# AirFlow_Sensor.net
KiCad netlist of a schematic drawn in EAGLE
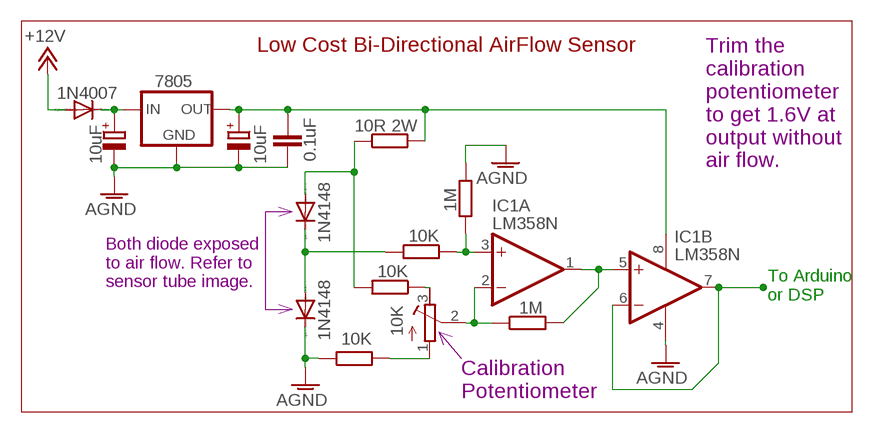
[diagram p0: schematic, sheet 1]

(export (version "E")
  (design (tool "Eeschema 10.0.6"))
  (components
    (comp (ref "C1")
      (value "0.1uF")
      (footprint "eagle-import:C025-025X050")
      (libsource (lib "eagle-import") (part "C-EU025-025X050"))
    )
    (comp (ref "C2")
      (value "10uF")
      (footprint "eagle-import:E2,5-6")
      (libsource (lib "eagle-import") (part "CPOL-EUE2.5-6"))
    )
    (comp (ref "C4")
      (value "10uF")
      (footprint "eagle-import:E2,5-6")
      (libsource (lib "eagle-import") (part "CPOL-EUE2.5-6"))
    )
    (comp (ref "CALIBRATION")
      (value "10K")
      (footprint "eagle-import:RTRIM64W")
      (libsource (lib "eagle-import") (part "R-TRIMM64W"))
    )
    (comp (ref "D2")
      (value "1N4148")
      (footprint "eagle-import:DO35-7")
      (libsource (lib "eagle-import") (part "1N4148DO35-7"))
    )
    (comp (ref "D3")
      (value "1N4148")
      (footprint "eagle-import:DO35-7")
      (libsource (lib "eagle-import") (part "1N4148DO35-7"))
    )
    (comp (ref "D4")
      (value "1N4007")
      (footprint "eagle-import:DO41-10")
      (libsource (lib "eagle-import") (part "1N4004"))
    )
    (comp (ref "IC1")
      (value "LM358N")
      (footprint "eagle-import:DIL08")
      (libsource (lib "eagle-import") (part "LM358N"))
    )
    (comp (ref "IC2")
      (value "7805")
      (footprint "eagle-import:78XXL")
      (libsource (lib "eagle-import") (part "78XXL"))
    )
    (comp (ref "R1")
      (value "10K")
      (footprint "eagle-import:0204_7")
      (libsource (lib "eagle-import") (part "R-EU_0204/7"))
    )
    (comp (ref "R2")
      (value "1M")
      (footprint "eagle-import:0204_7")
      (libsource (lib "eagle-import") (part "R-EU_0204/7"))
    )
    (comp (ref "R3")
      (value "1M")
      (footprint "eagle-import:0204_7")
      (libsource (lib "eagle-import") (part "R-EU_0204/7"))
    )
    (comp (ref "R4")
      (value "10K")
      (footprint "eagle-import:0204_7")
      (libsource (lib "eagle-import") (part "R-EU_0204/7"))
    )
    (comp (ref "R5")
      (value "10R 2W")
      (footprint "eagle-import:0204_7")
      (libsource (lib "eagle-import") (part "R-EU_0204/7"))
    )
    (comp (ref "R7")
      (value "10K")
      (footprint "eagle-import:0204_7")
      (libsource (lib "eagle-import") (part "R-EU_0204/7"))
    )
  )
  (nets
    (net (code "1") (name "+12V") (class "Default")
      (node (ref "D4") (pin "A") (pinfunction "A_A") (pintype "passive"))
    )
    (net (code "2") (name "AGND") (class "Default")
      (node (ref "C1") (pin "2") (pinfunction "2_2") (pintype "passive"))
      (node (ref "C2") (pin "-") (pinfunction "-_-") (pintype "passive"))
      (node (ref "C4") (pin "-") (pinfunction "-_-") (pintype "passive"))
      (node (ref "D2") (pin "C") (pinfunction "C_C") (pintype "passive"))
      (node (ref "IC1") (pin "4") (pinfunction "V-_4") (pintype "power_in"))
      (node (ref "IC2") (pin "GND") (pinfunction "GND_GND") (pintype "input"))
      (node (ref "R1") (pin "1") (pinfunction "1_1") (pintype "passive"))
      (node (ref "R3") (pin "2") (pinfunction "2_2") (pintype "passive"))
    )
    (net (code "3") (name "Net-(C2-Pad+)") (class "Default")
      (node (ref "C2") (pin "+") (pinfunction "+_+") (pintype "passive"))
      (node (ref "D4") (pin "C") (pinfunction "C_C") (pintype "passive"))
      (node (ref "IC2") (pin "IN") (pinfunction "IN_IN") (pintype "input"))
    )
    (net (code "4") (name "Net-(CALIBRATION-A)") (class "Default")
      (node (ref "CALIBRATION") (pin "1") (pinfunction "A_1") (pintype "passive"))
      (node (ref "R1") (pin "2") (pinfunction "2_2") (pintype "passive"))
    )
    (net (code "5") (name "Net-(CALIBRATION-E)") (class "Default")
      (node (ref "CALIBRATION") (pin "3") (pinfunction "E_3") (pintype "passive"))
      (node (ref "R7") (pin "1") (pinfunction "1_1") (pintype "passive"))
    )
    (net (code "6") (name "Net-(CALIBRATION-S)") (class "Default")
      (node (ref "CALIBRATION") (pin "2") (pinfunction "S_2") (pintype "passive"))
      (node (ref "IC1") (pin "2") (pinfunction "-IN_2") (pintype "input"))
      (node (ref "R2") (pin "1") (pinfunction "1_1") (pintype "passive"))
    )
    (net (code "7") (name "Net-(D2-PadA)") (class "Default")
      (node (ref "D2") (pin "A") (pinfunction "A_A") (pintype "passive"))
      (node (ref "D3") (pin "C") (pinfunction "C_C") (pintype "passive"))
      (node (ref "R4") (pin "2") (pinfunction "2_2") (pintype "passive"))
    )
    (net (code "8") (name "Net-(D3-PadA)") (class "Default")
      (node (ref "D3") (pin "A") (pinfunction "A_A") (pintype "passive"))
      (node (ref "R5") (pin "1") (pinfunction "1_1") (pintype "passive"))
      (node (ref "R7") (pin "2") (pinfunction "2_2") (pintype "passive"))
    )
    (net (code "9") (name "Net-(IC1A-+IN)") (class "Default")
      (node (ref "IC1") (pin "3") (pinfunction "+IN_3") (pintype "input"))
      (node (ref "R3") (pin "1") (pinfunction "1_1") (pintype "passive"))
      (node (ref "R4") (pin "1") (pinfunction "1_1") (pintype "passive"))
    )
    (net (code "10") (name "Net-(IC1A-OUT)") (class "Default")
      (node (ref "IC1") (pin "1") (pinfunction "OUT_1") (pintype "output"))
      (node (ref "IC1") (pin "5") (pinfunction "+IN_5") (pintype "input"))
      (node (ref "R2") (pin "2") (pinfunction "2_2") (pintype "passive"))
    )
    (net (code "11") (name "Net-(IC1B--IN)") (class "Default")
      (node (ref "IC1") (pin "6") (pinfunction "-IN_6") (pintype "input"))
      (node (ref "IC1") (pin "7") (pinfunction "OUT_7") (pintype "output"))
    )
    (net (code "12") (name "Net-(IC1C-V+)") (class "Default")
      (node (ref "C1") (pin "1") (pinfunction "1_1") (pintype "passive"))
      (node (ref "C4") (pin "+") (pinfunction "+_+") (pintype "passive"))
      (node (ref "IC1") (pin "8") (pinfunction "V+_8") (pintype "power_in"))
      (node (ref "IC2") (pin "OUT") (pinfunction "OUT_OUT") (pintype "passive"))
      (node (ref "R5") (pin "2") (pinfunction "2_2") (pintype "passive"))
    )
  )
)
